# schematic_big.net
KiCad netlist of a schematic drawn in Altium Designer
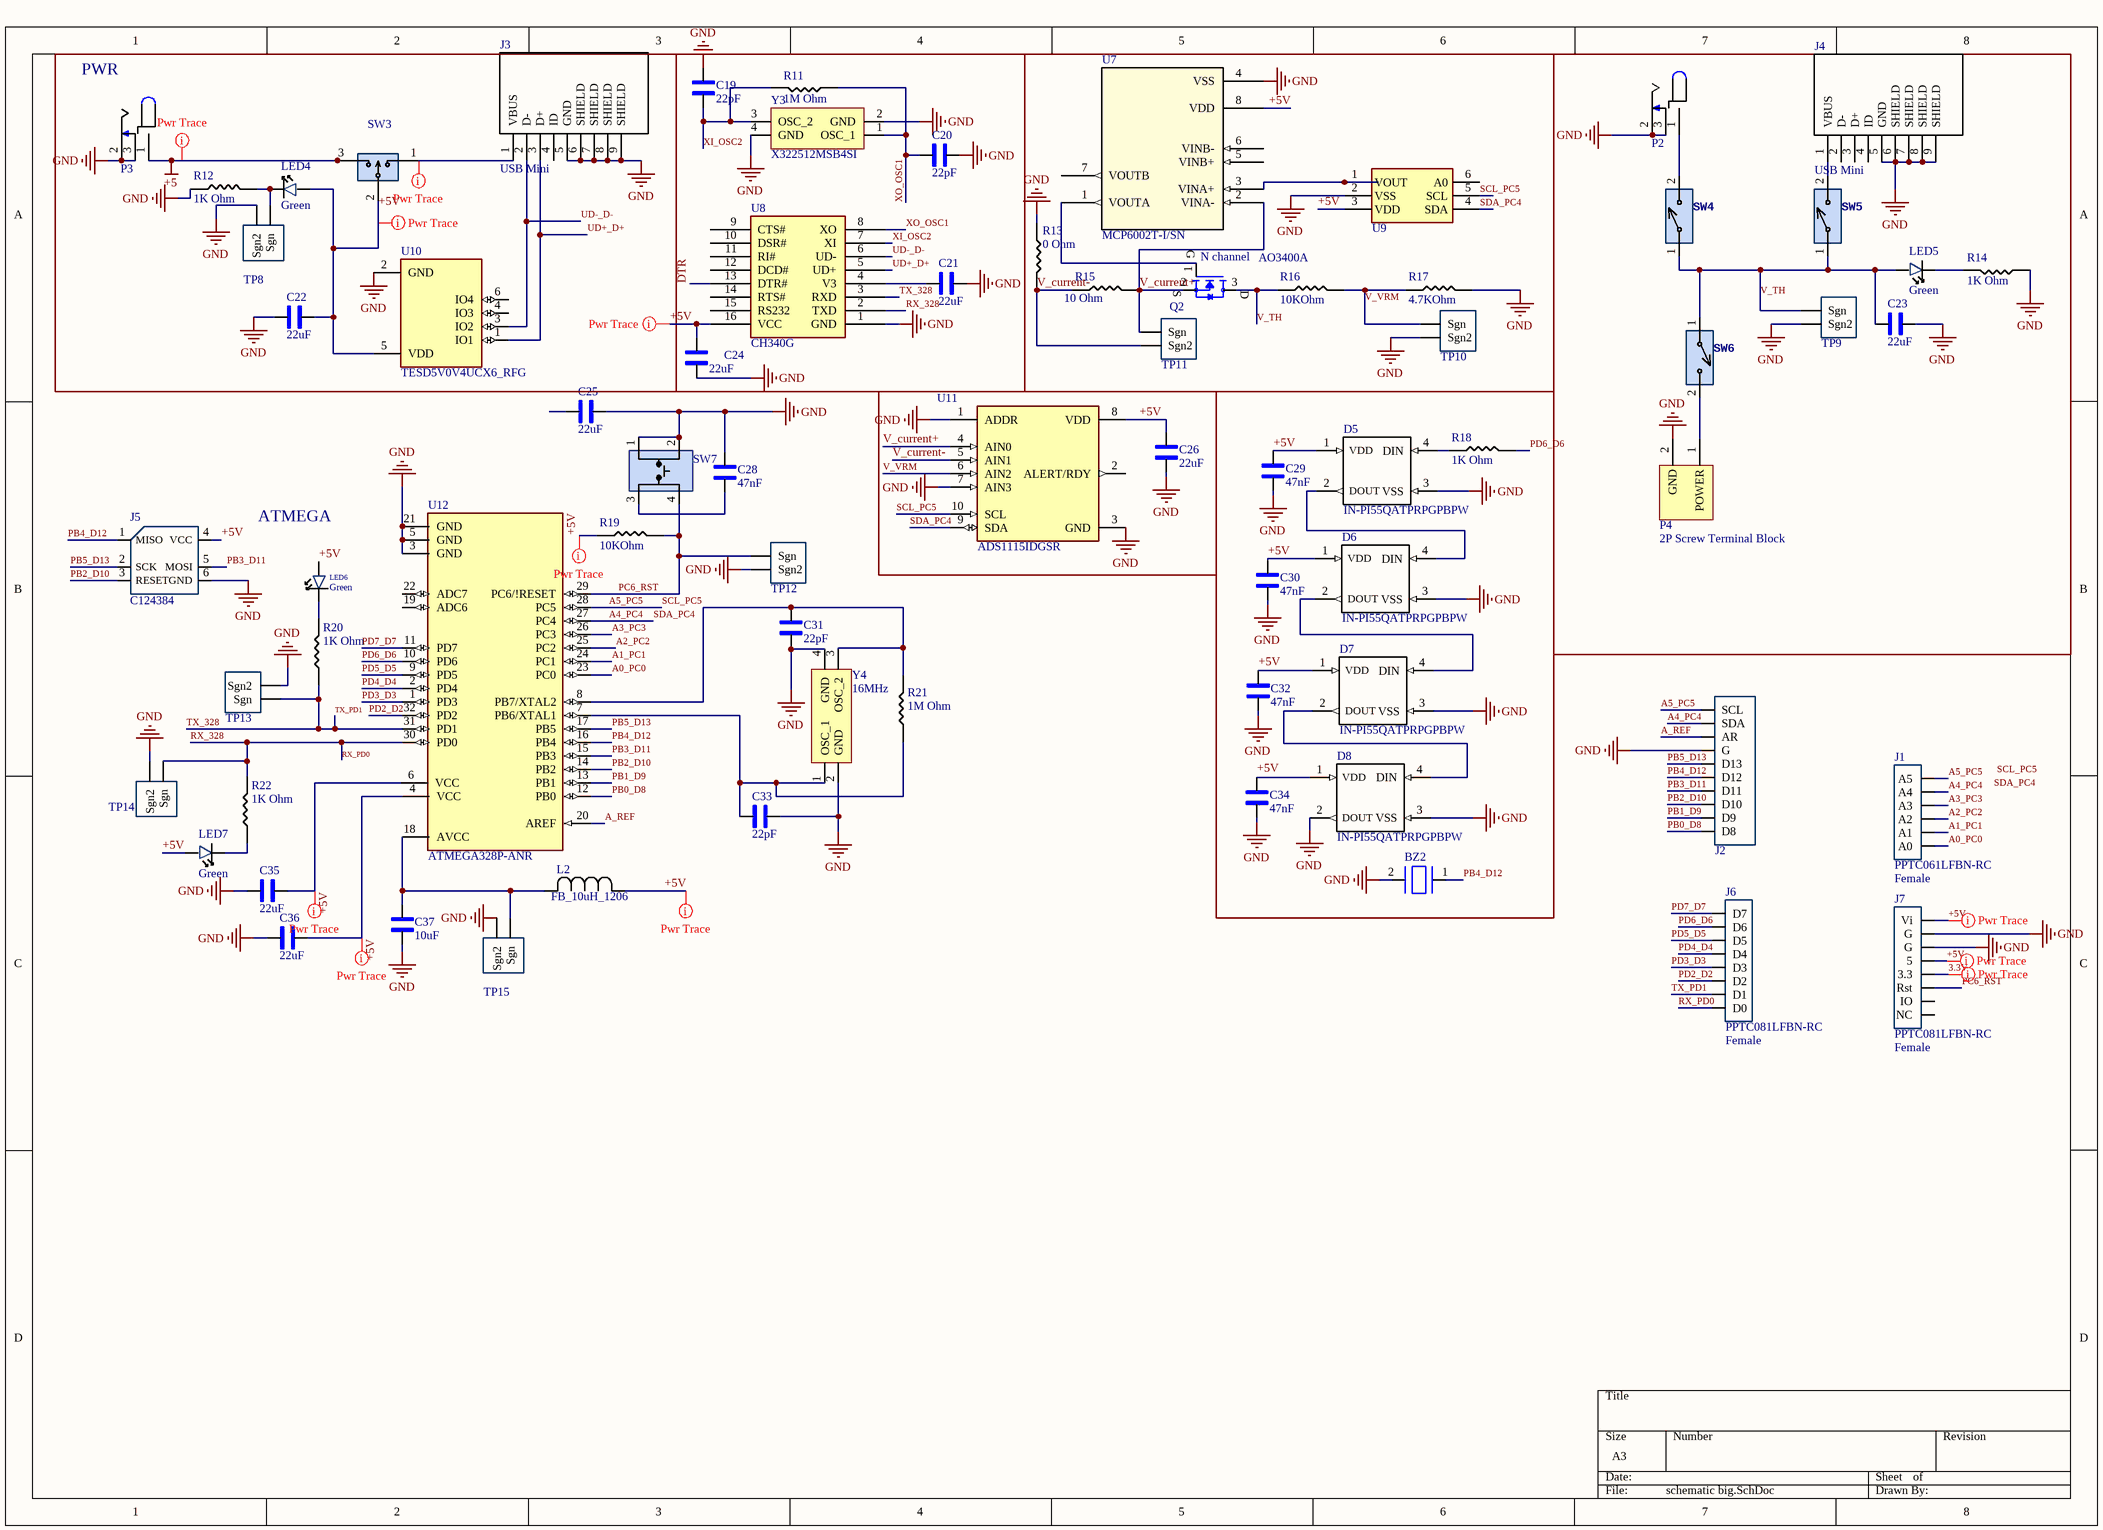
[diagram p0: schematic big.SchDoc]

(export (version "E")
  (design (tool "Eeschema 10.0.6"))
  (components
    (comp (ref "BZ2")
      (value "AT-1224-TWT-5V-2-R")
      (footprint "BUZZER- TH")
      (libsource (lib "ECEN5730Lib_2023_05_DS") (part "BUZZER_1"))
    )
    (comp (ref "C19")
      (value "22pF")
      (footprint "1206_Passive_Capacitor")
      (description "22pF ±5% 1kV C0G 1206 Multilayer Ceramic Capacitors MLCC - SMD/SMT RoHS")
      (fields (field (name "LCSC PART#") "C107174") (field (name "MFR PART #") "CC1206JKNPOCBN220"))
      (libsource (lib "ECEN5730Lib_2023_05_DS") (part "C_22pF_1206"))
    )
    (comp (ref "C20")
      (value "22pF")
      (footprint "1206_Passive_Capacitor")
      (description "22pF ±5% 1kV C0G 1206 Multilayer Ceramic Capacitors MLCC - SMD/SMT RoHS")
      (fields (field (name "LCSC PART#") "C107174") (field (name "MFR PART #") "CC1206JKNPOCBN220"))
      (libsource (lib "ECEN5730Lib_2023_05_DS") (part "C_22pF_1206"))
    )
    (comp (ref "C21")
      (value "22uF")
      (footprint "1206_Passive_Capacitor")
      (description "22uF ±10% 25V X5R 1206 Multilayer Ceramic Capacitors MLCC - SMD/SMT RoHS")
      (fields (field (name "MFR PART #") "CL31A226KAHNNNE") (field (name "LCSC PART#") "C12891"))
      (libsource (lib "ECEN5730Lib_2023_05_DS") (part "C_22uF_1206"))
    )
    (comp (ref "C22")
      (value "22uF")
      (footprint "1206_Passive_Capacitor")
      (description "22uF ±10% 25V X5R 1206 Multilayer Ceramic Capacitors MLCC - SMD/SMT RoHS")
      (fields (field (name "MFR PART #") "CL31A226KAHNNNE") (field (name "LCSC PART#") "C12891"))
      (libsource (lib "ECEN5730Lib_2023_05_DS") (part "C_22uF_1206"))
    )
    (comp (ref "C23")
      (value "22uF")
      (footprint "1206_Passive_Capacitor")
      (description "22uF ±10% 25V X5R 1206 Multilayer Ceramic Capacitors MLCC - SMD/SMT RoHS")
      (fields (field (name "MFR PART #") "CL31A226KAHNNNE") (field (name "LCSC PART#") "C12891"))
      (libsource (lib "ECEN5730Lib_2023_05_DS") (part "C_22uF_1206"))
    )
    (comp (ref "C24")
      (value "22uF")
      (footprint "1206_Passive_Capacitor")
      (description "22uF ±10% 25V X5R 1206 Multilayer Ceramic Capacitors MLCC - SMD/SMT RoHS")
      (fields (field (name "MFR PART #") "CL31A226KAHNNNE") (field (name "LCSC PART#") "C12891"))
      (libsource (lib "ECEN5730Lib_2023_05_DS") (part "C_22uF_1206"))
    )
    (comp (ref "C25")
      (value "22uF")
      (footprint "1206_Passive_Capacitor")
      (description "22uF ±10% 25V X5R 1206 Multilayer Ceramic Capacitors MLCC - SMD/SMT RoHS")
      (fields (field (name "MFR PART #") "CL31A226KAHNNNE") (field (name "LCSC PART#") "C12891"))
      (libsource (lib "ECEN5730Lib_2023_05_DS") (part "C_22uF_1206"))
    )
    (comp (ref "C26")
      (value "22uF")
      (footprint "1206_Passive_Capacitor")
      (description "22uF ±10% 25V X5R 1206 Multilayer Ceramic Capacitors MLCC - SMD/SMT RoHS")
      (fields (field (name "MFR PART #") "CL31A226KAHNNNE") (field (name "LCSC PART#") "C12891"))
      (libsource (lib "ECEN5730Lib_2023_05_DS") (part "C_22uF_1206"))
    )
    (comp (ref "C28")
      (value "47nF")
      (footprint "1206_Passive_Capacitor")
      (description "47nF ±5% 50V C0G 1206 Multilayer Ceramic Capacitors MLCC - SMD/SMT RoHS")
      (fields (field (name "LCSC PART#") "C21812") (field (name "MFR PART #") "GRM31M5C1H473JA01L"))
      (libsource (lib "ECEN5730Lib_2023_05_DS") (part "C_47nF_1206"))
    )
    (comp (ref "C29")
      (value "47nF")
      (footprint "1206_Passive_Capacitor")
      (description "47nF ±5% 50V C0G 1206 Multilayer Ceramic Capacitors MLCC - SMD/SMT RoHS")
      (fields (field (name "LCSC PART#") "C21812") (field (name "MFR PART #") "GRM31M5C1H473JA01L"))
      (libsource (lib "ECEN5730Lib_2023_05_DS") (part "C_47nF_1206"))
    )
    (comp (ref "C30")
      (value "47nF")
      (footprint "1206_Passive_Capacitor")
      (description "47nF ±5% 50V C0G 1206 Multilayer Ceramic Capacitors MLCC - SMD/SMT RoHS")
      (fields (field (name "LCSC PART#") "C21812") (field (name "MFR PART #") "GRM31M5C1H473JA01L"))
      (libsource (lib "ECEN5730Lib_2023_05_DS") (part "C_47nF_1206"))
    )
    (comp (ref "C31")
      (value "22pF")
      (footprint "1206_Passive_Capacitor")
      (description "22pF ±5% 1kV C0G 1206 Multilayer Ceramic Capacitors MLCC - SMD/SMT RoHS")
      (fields (field (name "LCSC PART#") "C107174") (field (name "MFR PART #") "CC1206JKNPOCBN220"))
      (libsource (lib "ECEN5730Lib_2023_05_DS") (part "C_22pF_1206"))
    )
    (comp (ref "C32")
      (value "47nF")
      (footprint "1206_Passive_Capacitor")
      (description "47nF ±5% 50V C0G 1206 Multilayer Ceramic Capacitors MLCC - SMD/SMT RoHS")
      (fields (field (name "LCSC PART#") "C21812") (field (name "MFR PART #") "GRM31M5C1H473JA01L"))
      (libsource (lib "ECEN5730Lib_2023_05_DS") (part "C_47nF_1206"))
    )
    (comp (ref "C33")
      (value "22pF")
      (footprint "1206_Passive_Capacitor")
      (description "22pF ±5% 1kV C0G 1206 Multilayer Ceramic Capacitors MLCC - SMD/SMT RoHS")
      (fields (field (name "LCSC PART#") "C107174") (field (name "MFR PART #") "CC1206JKNPOCBN220"))
      (libsource (lib "ECEN5730Lib_2023_05_DS") (part "C_22pF_1206"))
    )
    (comp (ref "C34")
      (value "47nF")
      (footprint "1206_Passive_Capacitor")
      (description "47nF ±5% 50V C0G 1206 Multilayer Ceramic Capacitors MLCC - SMD/SMT RoHS")
      (fields (field (name "LCSC PART#") "C21812") (field (name "MFR PART #") "GRM31M5C1H473JA01L"))
      (libsource (lib "ECEN5730Lib_2023_05_DS") (part "C_47nF_1206"))
    )
    (comp (ref "C35")
      (value "22uF")
      (footprint "1206_Passive_Capacitor")
      (description "22uF ±10% 25V X5R 1206 Multilayer Ceramic Capacitors MLCC - SMD/SMT RoHS")
      (fields (field (name "MFR PART #") "CL31A226KAHNNNE") (field (name "LCSC PART#") "C12891"))
      (libsource (lib "ECEN5730Lib_2023_05_DS") (part "C_22uF_1206"))
    )
    (comp (ref "C36")
      (value "22uF")
      (footprint "1206_Passive_Capacitor")
      (description "22uF ±10% 25V X5R 1206 Multilayer Ceramic Capacitors MLCC - SMD/SMT RoHS")
      (fields (field (name "MFR PART #") "CL31A226KAHNNNE") (field (name "LCSC PART#") "C12891"))
      (libsource (lib "ECEN5730Lib_2023_05_DS") (part "C_22uF_1206"))
    )
    (comp (ref "C37")
      (value "10uF")
      (footprint "1206_Passive_Capacitor")
      (description "10uF ±10% 50V X5R 1206 Multilayer Ceramic Capacitors MLCC - SMD/SMT RoHS")
      (fields (field (name "LCSC PART#") "C13585") (field (name "MFR PART #") "CL31A106KBHNNNE"))
      (libsource (lib "ECEN5730Lib_2023_05_DS") (part "C_10uF_1206"))
    )
    (comp (ref "D5")
      (value "IN-PI55QATPRPGPBPW")
      (footprint "SERIAL_LED - duplicate")
      (fields
        (field (name "LCSC PART#") "C2843785")
        (field (name "MFR PART #") "XL-5050RGBC-WS2812B")
        (field (name "MANUFACTURER") "XINGLIGHT")
      )
      (libsource (lib "ECEN5730Lib_2023_05_DS") (part "LED_Smart"))
    )
    (comp (ref "D6")
      (value "IN-PI55QATPRPGPBPW")
      (footprint "SERIAL_LED - duplicate")
      (fields
        (field (name "LCSC PART#") "C2843785")
        (field (name "MFR PART #") "XL-5050RGBC-WS2812B")
        (field (name "MANUFACTURER") "XINGLIGHT")
      )
      (libsource (lib "ECEN5730Lib_2023_05_DS") (part "LED_Smart"))
    )
    (comp (ref "D7")
      (value "IN-PI55QATPRPGPBPW")
      (footprint "SERIAL_LED - duplicate")
      (fields
        (field (name "LCSC PART#") "C2843785")
        (field (name "MFR PART #") "XL-5050RGBC-WS2812B")
        (field (name "MANUFACTURER") "XINGLIGHT")
      )
      (libsource (lib "ECEN5730Lib_2023_05_DS") (part "LED_Smart"))
    )
    (comp (ref "D8")
      (value "IN-PI55QATPRPGPBPW")
      (footprint "SERIAL_LED - duplicate")
      (fields
        (field (name "LCSC PART#") "C2843785")
        (field (name "MFR PART #") "XL-5050RGBC-WS2812B")
        (field (name "MANUFACTURER") "XINGLIGHT")
      )
      (libsource (lib "ECEN5730Lib_2023_05_DS") (part "LED_Smart"))
    )
    (comp (ref "J1")
      (value "PPTC061LFBN-RC")
      (footprint "6_PIN_ARD-Analog_100mil")
      (description "6 Position Header Connector 0.100\" (2.54mm) Through Hole Tin")
      (fields (field (name "LCSC PART#") "C40877") (field (name "ALTIUM_VALUE") "Female"))
      (libsource (lib "ECEN5730Lib_2023_05_DS") (part "JF_6_PIN_FEMA_ARD-Anolog"))
    )
    (comp (ref "J2")
      (value "PPTC101LFBN-RC")
      (footprint "10_PIN_ARDUINO_100MIL")
      (description "10 Position Header Connector 0.100\" (2.54mm) Through Hole Tin")
      (fields (field (name "LCSC PART#") "C225507"))
      (libsource (lib "ECEN5730Lib_2023_05_DS") (part "JF_10_PIN_FEMA_ARDUINO"))
    )
    (comp (ref "J3")
      (value "USB Mini")
      (footprint "USB_MINI_B")
      (description "Through Hole USB Connectors RoHS")
      (fields (field (name "LCSC PART#") "C46398") (field (name "MFR PART #") "920-462A2021D10102"))
      (libsource (lib "ECEN5730Lib_2023_05_DS") (part "J_USB_B_Mini"))
    )
    (comp (ref "J4")
      (value "USB Mini")
      (footprint "USB_MINI_B")
      (description "Through Hole USB Connectors RoHS")
      (fields (field (name "LCSC PART#") "C46398") (field (name "MFR PART #") "920-462A2021D10102"))
      (libsource (lib "ECEN5730Lib_2023_05_DS") (part "J_USB_B_Mini"))
    )
    (comp (ref "J5")
      (value "NRPN032PAEN-RC")
      (footprint "ICSP")
      (description "Connector Header Through Hole 6 position 0.079\" (2.00mm)")
      (fields (field (name "LCSC PART#") "C124384"))
      (libsource (lib "ECEN5730Lib_2023_05_DS") (part "J_ICSP"))
    )
    (comp (ref "J6")
      (value "PPTC081LFBN-RC")
      (footprint "8_PIN_ARD-DIG_100MIL")
      (description "8 Position Header Connector 0.100\" (2.54mm) Through Hole Tin")
      (fields (field (name "LCSC PART#") "C27438") (field (name "ALTIUM_VALUE") "Female"))
      (libsource (lib "ECEN5730Lib_2023_05_DS") (part "JF_8_PIN_FEMA_ARD-Dig"))
    )
    (comp (ref "J7")
      (value "PPTC081LFBN-RC")
      (footprint "8_PIN_ARD-PWR_100MIL")
      (description "8 Position Header Connector 0.100\" (2.54mm) Through Hole Tin")
      (fields (field (name "LCSC PART#") "C27438") (field (name "ALTIUM_VALUE") "Female"))
      (libsource (lib "ECEN5730Lib_2023_05_DS") (part "JF_8_PIN_FEMA_ARD-Pwr"))
    )
    (comp (ref "L2")
      (value "FB_10uH_1206")
      (footprint "AIML-1206_ABR-M")
      (description "25mA 10uH ±10% 800mΩ 1206  Inductors (SMD) ROHS")
      (fields (field (name "MFR PART #") "CMI321609X100KT") (field (name "LCSC PART#") "C1051"))
      (libsource (lib "ECEN5730Lib_2023_05_DS") (part "FB_10uH_1206"))
    )
    (comp (ref "LED4")
      (value "Green")
      (footprint "LED_1206")
      (description "Green 513~528nm 1206 Light Emitting Diodes (LED) RoHS")
      (fields (field (name "MFR PART #") "SZYY1206G") (field (name "LCSC PART#") "C434439"))
      (libsource (lib "ECEN5730Lib_2023_05_DS") (part "LED_GREEN_1206"))
    )
    (comp (ref "LED5")
      (value "Green")
      (footprint "LED_1206")
      (description "Green 513~528nm 1206 Light Emitting Diodes (LED) RoHS")
      (fields (field (name "MFR PART #") "SZYY1206G") (field (name "LCSC PART#") "C434439"))
      (libsource (lib "ECEN5730Lib_2023_05_DS") (part "LED_GREEN_1206"))
    )
    (comp (ref "LED6")
      (value "Green")
      (footprint "LED_1206")
      (description "Green 513~528nm 1206 Light Emitting Diodes (LED) RoHS")
      (fields (field (name "MFR PART #") "SZYY1206G") (field (name "LCSC PART#") "C434439"))
      (libsource (lib "ECEN5730Lib_2023_05_DS") (part "LED_GREEN_1206"))
    )
    (comp (ref "LED7")
      (value "Green")
      (footprint "LED_1206")
      (description "Green 513~528nm 1206 Light Emitting Diodes (LED) RoHS")
      (fields (field (name "MFR PART #") "SZYY1206G") (field (name "LCSC PART#") "C434439"))
      (libsource (lib "ECEN5730Lib_2023_05_DS") (part "LED_GREEN_1206"))
    )
    (comp (ref "P2")
      (value "Power Jack")
      (footprint "Power_Jack")
      (description "Power Barrel Connector Jack 2.10mm ID (0.083\"), 5.50mm OD (0.217\") Through Hole, Right Angle")
      (fields (field (name "MFR PART #") "PJ-102A") (field (name "LCSC PART#") "C136744"))
      (libsource (lib "ECEN5730Lib_2023_05_DS") (part "P_Power Jack"))
    )
    (comp (ref "P3")
      (value "Power Jack")
      (footprint "Power_Jack")
      (description "Power Barrel Connector Jack 2.10mm ID (0.083\"), 5.50mm OD (0.217\") Through Hole, Right Angle")
      (fields (field (name "MFR PART #") "PJ-102A") (field (name "LCSC PART#") "C136744"))
      (libsource (lib "ECEN5730Lib_2023_05_DS") (part "P_Power Jack"))
    )
    (comp (ref "P4")
      (value "2P Screw Terminal Block")
      (footprint "P_Terminal block 3.5mm-pitch")
      (description "Green Straight pin 3.5mm  pitch; P=3.5mm  Screw terminal ROHS")
      (fields (field (name "MFR PART #") "KF350-3.5-2P") (field (name "MANUFACTURER") "Cixi Kefa Elec"))
      (libsource (lib "ECEN5730Lib_2023_05_DS") (part "P_Terminal block"))
    )
    (comp (ref "Q2")
      (value "AO3400A")
      (footprint "N-MOSFET")
      (description "MOSFET N Trench 30V 5.7A 1.5V @ 250uA 26.5 m? @ 5.7A,10V SOT-23-3L RoHS")
      (fields (field (name "LCSC PART#") "C20917") (field (name "ALTIUM_VALUE") "N channel"))
      (libsource (lib "ECEN5730Lib_2023_05_DS") (part "Q_Nch_MOSFET"))
    )
    (comp (ref "R11")
      (value "1M Ohm")
      (footprint "1206_Passive_Resitor")
      (description "CHIP RESISTOR - SURFACE MOUNT 1MOHMS ±1% 1/4W 1206 ROHS")
      (fields (field (name "MFR PART #") "RMCF1206JT1M00") (field (name "LCSC PART#") "C17927"))
      (libsource (lib "ECEN5730Lib_2023_05_DS") (part "R_1M_1206"))
    )
    (comp (ref "R12")
      (value "1K Ohm")
      (footprint "1206_Passive_Resitor")
      (description "CHIP RESISTOR - SURFACE MOUNT 1KOHMS ±1% 1/4W 1206 ROHS")
      (fields (field (name "MFR PART #") "RNCP1206FTD1K00CT") (field (name "LCSC PART#") "C4410"))
      (libsource (lib "ECEN5730Lib_2023_05_DS") (part "R_1K_1206"))
    )
    (comp (ref "R13")
      (value "0 Ohm")
      (footprint "1206_Passive_Resitor")
      (description "CHIP RESISTOR - SURFACE MOUNT 0OHMS ±1% 1/4W 1206 ROHS")
      (fields (field (name "MFR PART #") "1206W4F0000T5E") (field (name "LCSC PART#") "C17888"))
      (libsource (lib "ECEN5730Lib_2023_05_DS") (part "R_0Ohm_1206"))
    )
    (comp (ref "R14")
      (value "1K Ohm")
      (footprint "1206_Passive_Resitor")
      (description "CHIP RESISTOR - SURFACE MOUNT 1KOHMS ±1% 1/4W 1206 ROHS")
      (fields (field (name "MFR PART #") "RNCP1206FTD1K00CT") (field (name "LCSC PART#") "C4410"))
      (libsource (lib "ECEN5730Lib_2023_05_DS") (part "R_1K_1206"))
    )
    (comp (ref "R15")
      (value "10 Ohm")
      (footprint "1206_Passive_Resitor")
      (description "CHIP RESISTOR - SURFACE MOUNT 0.1OHMS ±1% 1/4W 1206 ROHS")
      (fields (field (name "MFR PART #") "1206W4F100JT5E") (field (name "LCSC PART#") "C17903"))
      (libsource (lib "ECEN5730Lib_2023_05_DS") (part "R_10Ohm_1206"))
    )
    (comp (ref "R16")
      (value "10KOhm")
      (footprint "1206_Passive_Resitor")
      (description "10 kOhms ±5% 0.25W, 1/4W Chip Resistor 1206 (3216 Metric) Automotive AEC-Q200 Thick Film")
      (fields (field (name "MFR PART #") "RMCF1206FT10K0") (field (name "LCSC PART#") "C17902"))
      (libsource (lib "ECEN5730Lib_2023_05_DS") (part "R_10KOhm_1206"))
    )
    (comp (ref "R17")
      (value "4.7KOhm")
      (footprint "1206_Passive_Resitor")
      (description "4.7kΩ ±1% 0.25W ±100ppm/℃ 1206 Chip Resistor - Surface Mount RoHS")
      (fields (field (name "LCSC PART#") "C17936") (field (name "MFR PART #") "1206W4F4701T5E"))
      (libsource (lib "ECEN5730Lib_2023_05_DS") (part "R_4.7k_1206"))
    )
    (comp (ref "R18")
      (value "1K Ohm")
      (footprint "1206_Passive_Resitor")
      (description "CHIP RESISTOR - SURFACE MOUNT 1KOHMS ±1% 1/4W 1206 ROHS")
      (fields (field (name "MFR PART #") "RNCP1206FTD1K00CT") (field (name "LCSC PART#") "C4410"))
      (libsource (lib "ECEN5730Lib_2023_05_DS") (part "R_1K_1206"))
    )
    (comp (ref "R19")
      (value "10KOhm")
      (footprint "1206_Passive_Resitor")
      (description "10 kOhms ±5% 0.25W, 1/4W Chip Resistor 1206 (3216 Metric) Automotive AEC-Q200 Thick Film")
      (fields (field (name "MFR PART #") "RMCF1206FT10K0") (field (name "LCSC PART#") "C17902"))
      (libsource (lib "ECEN5730Lib_2023_05_DS") (part "R_10KOhm_1206"))
    )
    (comp (ref "R20")
      (value "1K Ohm")
      (footprint "1206_Passive_Resitor")
      (description "CHIP RESISTOR - SURFACE MOUNT 1KOHMS ±1% 1/4W 1206 ROHS")
      (fields (field (name "MFR PART #") "RNCP1206FTD1K00CT") (field (name "LCSC PART#") "C4410"))
      (libsource (lib "ECEN5730Lib_2023_05_DS") (part "R_1K_1206"))
    )
    (comp (ref "R21")
      (value "1M Ohm")
      (footprint "1206_Passive_Resitor")
      (description "CHIP RESISTOR - SURFACE MOUNT 1MOHMS ±1% 1/4W 1206 ROHS")
      (fields (field (name "MFR PART #") "RMCF1206JT1M00") (field (name "LCSC PART#") "C17927"))
      (libsource (lib "ECEN5730Lib_2023_05_DS") (part "R_1M_1206"))
    )
    (comp (ref "R22")
      (value "1K Ohm")
      (footprint "1206_Passive_Resitor")
      (description "CHIP RESISTOR - SURFACE MOUNT 1KOHMS ±1% 1/4W 1206 ROHS")
      (fields (field (name "MFR PART #") "RNCP1206FTD1K00CT") (field (name "LCSC PART#") "C4410"))
      (libsource (lib "ECEN5730Lib_2023_05_DS") (part "R_1K_1206"))
    )
    (comp (ref "SW3")
      (value "PREC003SAAN-RC")
      (footprint "3_PIN_100mil")
      (description "Connector Header Through Hole 3 position 0.100\" (2.54mm)")
      (fields (field (name "LCSC PART#") "C49257"))
      (libsource (lib "ECEN5730Lib_2023_05_DS") (part "SW_3Pin_100mil_Switch"))
    )
    (comp (ref "SW4")
      (value "SW_2Pin_100mil_Switch")
      (footprint "2Pin-Header-Conn")
      (description "2Pin Header")
      (fields (field (name "LCSC PART#") "C124375"))
      (libsource (lib "ECEN5730Lib_2023_05_DS") (part "SW_2Pin_100mil_Switch"))
    )
    (comp (ref "SW5")
      (value "SW_2Pin_100mil_Switch")
      (footprint "2Pin-Header-Conn")
      (description "2Pin Header")
      (fields (field (name "LCSC PART#") "C124375"))
      (libsource (lib "ECEN5730Lib_2023_05_DS") (part "SW_2Pin_100mil_Switch"))
    )
    (comp (ref "SW6")
      (value "SW_2Pin_100mil_Switch")
      (footprint "2Pin-Header-Conn")
      (description "2Pin Header")
      (fields (field (name "LCSC PART#") "C124375"))
      (libsource (lib "") (part "SW_2Pin_100mil_Switch_1"))
    )
    (comp (ref "SW7")
      (value "TL3305AF160QG")
      (footprint "Switch_JLC")
      (description "Tactile Switch SPST-NO Top Actuated Surface Mount")
      (fields (field (name "MFR PART #") "KH-4.5X4.5X4.3H-STM") (field (name "LCSC PART#") "C2837550"))
      (libsource (lib "ECEN5730Lib_2023_05_DS") (part "SW_Push_Button_JLC"))
    )
    (comp (ref "TP8")
      (value "10x Probe TP")
      (footprint "TP_Diff_Probe")
      (description "Test Point 300 mil centers")
      (libsource (lib "ECEN5730Lib_2023_05_DS") (part "TP_Diff_Probe"))
    )
    (comp (ref "TP9")
      (value "10x Probe TP")
      (footprint "TP_Diff_Probe")
      (description "Test Point 300 mil centers")
      (libsource (lib "") (part "TP_Diff_Probe_1"))
    )
    (comp (ref "TP10")
      (value "10x Probe TP")
      (footprint "TP_Diff_Probe")
      (description "Test Point 300 mil centers")
      (libsource (lib "") (part "TP_Diff_Probe_1"))
    )
    (comp (ref "TP11")
      (value "10x Probe TP")
      (footprint "TP_Diff_Probe")
      (description "Test Point 300 mil centers")
      (libsource (lib "") (part "TP_Diff_Probe_1"))
    )
    (comp (ref "TP12")
      (value "10x Probe TP")
      (footprint "TP_Diff_Probe")
      (description "Test Point 300 mil centers")
      (libsource (lib "") (part "TP_Diff_Probe_1"))
    )
    (comp (ref "TP13")
      (value "10x Probe TP")
      (footprint "TP_Diff_Probe")
      (description "Test Point 300 mil centers")
      (libsource (lib "") (part "TP_Diff_Probe_2"))
    )
    (comp (ref "TP14")
      (value "10x Probe TP")
      (footprint "TP_Diff_Probe")
      (description "Test Point 300 mil centers")
      (libsource (lib "ECEN5730Lib_2023_05_DS") (part "TP_Diff_Probe"))
    )
    (comp (ref "TP15")
      (value "10x Probe TP")
      (footprint "TP_Diff_Probe")
      (description "Test Point 300 mil centers")
      (libsource (lib "ECEN5730Lib_2023_05_DS") (part "TP_Diff_Probe"))
    )
    (comp (ref "U7")
      (value "MCP6002T-I/SN")
      (footprint "SOIC127P600X175-8N")
      (description "0.6 V/us 2 1MHz 1.8V ~ 6V 100μA General Purpose SOIC-8_150mil  Operational Amplifier ROHS")
      (fields (field (name "MFR") "Microchip") (field (name "LCSC PART#") "C7377"))
      (libsource (lib "ECEN5730Lib_2023_05_DS") (part "U_MCP6002T-I/SN"))
    )
    (comp (ref "U8")
      (value "CH340G")
      (footprint "USB to serial")
      (description "Transceiver USB 2.0 2Mbps SOP-16_150mil USB ICs RoHS")
      (fields (field (name "LCSC PART#") "C14267"))
      (libsource (lib "ECEN5730Lib_2023_05_DS") (part "U_USBtoSerial"))
    )
    (comp (ref "U9")
      (value "DAC IC")
      (footprint "MCP4725")
      (description "IC DAC 12BIT V-OUT SOT23-6")
      (fields (field (name "LCSC PART#") "C144198") (field (name "MFR PART #") "MCP4725A0T-E/CH"))
      (libsource (lib "ECEN5730Lib_2023_05_DS") (part "U_MCP4725A0T-E/CH"))
    )
    (comp (ref "U10")
      (value "TESD5V0V4UCX6_RFG")
      (footprint "SOT95P280X145-6N")
      (description "SOT-26, 5V, 75W, 0.6pF, ESD Protection")
      (fields (field (name "MF") "Taiwan Semiconductor") (field (name "MP") "TESD5V0V4UCX6 RFG"))
      (libsource (lib "TESD5V0V4UCX6_RFG") (part "TESD5V0V4UCX6_RFG"))
    )
    (comp (ref "U11")
      (value "ADS1115IDGSR")
      (footprint "ADC_ADS1115IDGSR")
      (description "16-Bit ADC with Integrated MUX, PGA, Comparator, Oscillator, and Reference 10-VSSOP -40 to 125")
      (fields (field (name "LCSC PART#") "C37593"))
      (libsource (lib "ECEN5730Lib_2023_05_DS") (part "U_ADC_ADS1115IDGSR"))
    )
    (comp (ref "U12")
      (value "ATMEGA328P-ANR")
      (footprint "ATMega328P")
      (description "AVR AVR® ATmega Microcontroller IC 8-Bit 20MHz 32KB (16K x 16) FLASH 32-TQFP (7x7)")
      (fields (field (name "MFR PART #") "ATMEGA328P-AU") (field (name "LCSC PART#") "C14877"))
      (libsource (lib "ECEN5730Lib_2023_05_DS") (part "U_ATMega328P"))
    )
    (comp (ref "Y3")
      (value "X322512MSB4SI")
      (footprint "Crystal resonator")
      (description "SMD Crystal Resonators 12MHz ±10ppm SMD-3225_4P RoHS")
      (fields (field (name "LCSC PART#") "C9002"))
      (libsource (lib "ECEN5730Lib_2023_05_DS") (part "X_12MHz_Res"))
    )
    (comp (ref "Y4")
      (value "16MHz")
      (footprint "Crystal resonator")
      (description "±10ppm 16000000Hz -40℃~85℃ 贴片无源晶振 60Ω 9pF SMD3225-4P Crystals ROHS")
      (fields (field (name "LCSC PART#") "C13738") (field (name "MFR PART #") "X322516MLB4SI"))
      (libsource (lib "ECEN5730Lib_2023_05_DS") (part "X_16Mhz_Res"))
    )
  )
  (nets
    (net (code "1") (name "+5") (class "Default")
      (node (ref "P3") (pin "1") (pinfunction "1_1") (pintype "power_in"))
      (node (ref "SW3") (pin "3") (pinfunction "3_3") (pintype "passive"))
    )
    (net (code "2") (name "/+5V") (class "Default")
      (node (ref "C22") (pin "2") (pinfunction "2_2") (pintype "passive"))
      (node (ref "C24") (pin "2") (pinfunction "2_2") (pintype "passive"))
      (node (ref "C26") (pin "2") (pinfunction "2_2") (pintype "passive"))
      (node (ref "C29") (pin "2") (pinfunction "2_2") (pintype "passive"))
      (node (ref "C30") (pin "2") (pinfunction "2_2") (pintype "passive"))
      (node (ref "C35") (pin "2") (pinfunction "2_2") (pintype "passive"))
      (node (ref "C36") (pin "2") (pinfunction "2_2") (pintype "passive"))
      (node (ref "D5") (pin "1") (pinfunction "VDD_1") (pintype "input"))
      (node (ref "D6") (pin "1") (pinfunction "VDD_1") (pintype "input"))
      (node (ref "J5") (pin "4") (pinfunction "VCC_4") (pintype "passive"))
      (node (ref "J7") (pin "5") (pinfunction "5_5") (pintype "passive"))
      (node (ref "J7") (pin "8") (pinfunction "Vi_8") (pintype "passive"))
      (node (ref "L2") (pin "1") (pinfunction "1_1") (pintype "passive"))
      (node (ref "LED4") (pin "1") (pinfunction "1_1") (pintype "passive"))
      (node (ref "LED6") (pin "1") (pinfunction "1_1") (pintype "passive"))
      (node (ref "LED7") (pin "1") (pinfunction "1_1") (pintype "passive"))
      (node (ref "R19") (pin "1") (pinfunction "1_1") (pintype "passive"))
      (node (ref "SW3") (pin "2") (pinfunction "2_2") (pintype "passive"))
      (node (ref "U10") (pin "5") (pinfunction "VDD_5") (pintype "power_in"))
      (node (ref "U11") (pin "8") (pinfunction "VDD_8") (pintype "power_in"))
      (node (ref "U12") (pin "4") (pinfunction "VCC_4") (pintype "power_in"))
      (node (ref "U12") (pin "6") (pinfunction "VCC_6") (pintype "power_in"))
      (node (ref "U7") (pin "8") (pinfunction "VDD_8") (pintype "passive"))
      (node (ref "U8") (pin "16") (pinfunction "VCC_16") (pintype "passive"))
      (node (ref "U9") (pin "3") (pinfunction "VDD_3") (pintype "passive"))
    )
    (net (code "3") (name "/3.3V") (class "Default")
      (node (ref "J7") (pin "4") (pinfunction "3.3_4") (pintype "passive"))
    )
    (net (code "4") (name "/A0_PC0") (class "Default")
      (node (ref "J1") (pin "1") (pinfunction "A0_1") (pintype "passive"))
      (node (ref "U12") (pin "23") (pinfunction "PC0_23") (pintype "bidirectional"))
    )
    (net (code "5") (name "/A1_PC1") (class "Default")
      (node (ref "J1") (pin "2") (pinfunction "A1_2") (pintype "passive"))
      (node (ref "U12") (pin "24") (pinfunction "PC1_24") (pintype "bidirectional"))
    )
    (net (code "6") (name "/A2_PC2") (class "Default")
      (node (ref "J1") (pin "3") (pinfunction "A2_3") (pintype "passive"))
      (node (ref "U12") (pin "25") (pinfunction "PC2_25") (pintype "bidirectional"))
    )
    (net (code "7") (name "/A3_PC3") (class "Default")
      (node (ref "J1") (pin "4") (pinfunction "A3_4") (pintype "passive"))
      (node (ref "U12") (pin "26") (pinfunction "PC3_26") (pintype "bidirectional"))
    )
    (net (code "8") (name "/A4_PC4") (class "Default")
      (node (ref "J1") (pin "5") (pinfunction "A4_5") (pintype "passive"))
      (node (ref "J2") (pin "2") (pinfunction "SDA_2") (pintype "passive"))
      (node (ref "U11") (pin "9") (pinfunction "SDA_9") (pintype "bidirectional"))
      (node (ref "U12") (pin "27") (pinfunction "PC4_27") (pintype "bidirectional"))
      (node (ref "U9") (pin "4") (pinfunction "SDA_4") (pintype "passive"))
    )
    (net (code "9") (name "/A5_PC5") (class "Default")
      (node (ref "J1") (pin "6") (pinfunction "A5_6") (pintype "passive"))
      (node (ref "J2") (pin "1") (pinfunction "SCL_1") (pintype "passive"))
      (node (ref "U11") (pin "10") (pinfunction "SCL_10") (pintype "input"))
      (node (ref "U12") (pin "28") (pinfunction "PC5_28") (pintype "bidirectional"))
      (node (ref "U9") (pin "5") (pinfunction "SCL_5") (pintype "passive"))
    )
    (net (code "10") (name "/A_REF") (class "Default")
      (node (ref "J2") (pin "3") (pinfunction "AR_3") (pintype "passive"))
      (node (ref "U12") (pin "20") (pinfunction "AREF_20") (pintype "input"))
    )
    (net (code "11") (name "/DTR") (class "Default")
      (node (ref "U8") (pin "13") (pinfunction "DTR#_13") (pintype "passive"))
    )
    (net (code "12") (name "/PB0_D8") (class "Default")
      (node (ref "J2") (pin "10") (pinfunction "D8_10") (pintype "passive"))
      (node (ref "U12") (pin "12") (pinfunction "PB0_12") (pintype "bidirectional"))
    )
    (net (code "13") (name "/PB1_D9") (class "Default")
      (node (ref "J2") (pin "9") (pinfunction "D9_9") (pintype "passive"))
      (node (ref "U12") (pin "13") (pinfunction "PB1_13") (pintype "bidirectional"))
    )
    (net (code "14") (name "/PB2_D10") (class "Default")
      (node (ref "J2") (pin "8") (pinfunction "D10_8") (pintype "passive"))
      (node (ref "J5") (pin "3") (pinfunction "RESET_3") (pintype "passive"))
      (node (ref "U12") (pin "14") (pinfunction "PB2_14") (pintype "bidirectional"))
    )
    (net (code "15") (name "/PB3_D11") (class "Default")
      (node (ref "J2") (pin "7") (pinfunction "D11_7") (pintype "passive"))
      (node (ref "J5") (pin "5") (pinfunction "MOSI_5") (pintype "passive"))
      (node (ref "U12") (pin "15") (pinfunction "PB3_15") (pintype "bidirectional"))
    )
    (net (code "16") (name "/PB4_D12") (class "Default")
      (node (ref "BZ2") (pin "1") (pinfunction "BZ1_1") (pintype "passive"))
      (node (ref "J2") (pin "6") (pinfunction "D12_6") (pintype "passive"))
      (node (ref "J5") (pin "1") (pinfunction "MISO_1") (pintype "passive"))
      (node (ref "U12") (pin "16") (pinfunction "PB4_16") (pintype "bidirectional"))
    )
    (net (code "17") (name "/PB5_D13") (class "Default")
      (node (ref "J2") (pin "5") (pinfunction "D13_5") (pintype "passive"))
      (node (ref "J5") (pin "2") (pinfunction "SCK_2") (pintype "passive"))
      (node (ref "U12") (pin "17") (pinfunction "PB5_17") (pintype "bidirectional"))
    )
    (net (code "18") (name "/PC6_RST") (class "Default")
      (node (ref "J7") (pin "3") (pinfunction "Rst_3") (pintype "passive"))
      (node (ref "R19") (pin "2") (pinfunction "2_2") (pintype "passive"))
      (node (ref "SW7") (pin "4") (pinfunction "4_4") (pintype "passive"))
      (node (ref "TP12") (pin "1") (pinfunction "Sgn_1") (pintype "passive"))
      (node (ref "U12") (pin "29") (pinfunction "PC6/!RESET_29") (pintype "bidirectional"))
    )
    (net (code "19") (name "/PD2_D2") (class "Default")
      (node (ref "J6") (pin "6") (pinfunction "D2_6") (pintype "passive"))
      (node (ref "U12") (pin "32") (pinfunction "PD2_32") (pintype "bidirectional"))
    )
    (net (code "20") (name "/PD3_D3") (class "Default")
      (node (ref "J6") (pin "5") (pinfunction "D3_5") (pintype "passive"))
      (node (ref "U12") (pin "1") (pinfunction "PD3_1") (pintype "bidirectional"))
    )
    (net (code "21") (name "/PD4_D4") (class "Default")
      (node (ref "J6") (pin "4") (pinfunction "D4_4") (pintype "passive"))
      (node (ref "U12") (pin "2") (pinfunction "PD4_2") (pintype "bidirectional"))
    )
    (net (code "22") (name "/PD5_D5") (class "Default")
      (node (ref "J6") (pin "3") (pinfunction "D5_3") (pintype "passive"))
      (node (ref "U12") (pin "9") (pinfunction "PD5_9") (pintype "bidirectional"))
    )
    (net (code "23") (name "/PD6_D6") (class "Default")
      (node (ref "J6") (pin "2") (pinfunction "D6_2") (pintype "passive"))
      (node (ref "R18") (pin "2") (pinfunction "2_2") (pintype "passive"))
      (node (ref "U12") (pin "10") (pinfunction "PD6_10") (pintype "bidirectional"))
    )
    (net (code "24") (name "/PD7_D7") (class "Default")
      (node (ref "J6") (pin "1") (pinfunction "D7_1") (pintype "passive"))
      (node (ref "U12") (pin "11") (pinfunction "PD7_11") (pintype "bidirectional"))
    )
    (net (code "25") (name "/RX_328") (class "Default")
      (node (ref "J6") (pin "8") (pinfunction "D0_8") (pintype "passive"))
      (node (ref "R22") (pin "2") (pinfunction "2_2") (pintype "passive"))
      (node (ref "TP14") (pin "1") (pinfunction "Sgn_1") (pintype "passive"))
      (node (ref "U12") (pin "30") (pinfunction "PD0_30") (pintype "bidirectional"))
      (node (ref "U8") (pin "2") (pinfunction "TXD_2") (pintype "passive"))
    )
    (net (code "26") (name "/TX_328") (class "Default")
      (node (ref "J6") (pin "7") (pinfunction "D1_7") (pintype "passive"))
      (node (ref "R20") (pin "1") (pinfunction "1_1") (pintype "passive"))
      (node (ref "TP13") (pin "1") (pinfunction "Sgn_1") (pintype "passive"))
      (node (ref "U12") (pin "31") (pinfunction "PD1_31") (pintype "bidirectional"))
      (node (ref "U8") (pin "3") (pinfunction "RXD_3") (pintype "passive"))
    )
    (net (code "27") (name "/UD+_D+") (class "Default")
      (node (ref "J3") (pin "3") (pinfunction "D+_3") (pintype "passive"))
      (node (ref "U10") (pin "1") (pinfunction "IO1_1") (pintype "bidirectional"))
      (node (ref "U8") (pin "5") (pinfunction "UD+_5") (pintype "passive"))
    )
    (net (code "28") (name "/UD-_D-") (class "Default")
      (node (ref "J3") (pin "2") (pinfunction "D-_2") (pintype "passive"))
      (node (ref "U10") (pin "3") (pinfunction "IO2_3") (pintype "bidirectional"))
      (node (ref "U8") (pin "6") (pinfunction "UD-_6") (pintype "passive"))
    )
    (net (code "29") (name "/V_TH") (class "Default")
      (node (ref "C23") (pin "2") (pinfunction "2_2") (pintype "passive"))
      (node (ref "LED5") (pin "1") (pinfunction "1_1") (pintype "passive"))
      (node (ref "Q2") (pin "3") (pinfunction "D_3") (pintype "passive"))
      (node (ref "R16") (pin "1") (pinfunction "1_1") (pintype "passive"))
      (node (ref "SW4") (pin "1") (pinfunction "1_1") (pintype "passive"))
      (node (ref "SW5") (pin "1") (pinfunction "1_1") (pintype "passive"))
      (node (ref "SW6") (pin "1") (pinfunction "1_1") (pintype "passive"))
      (node (ref "TP9") (pin "1") (pinfunction "Sgn_1") (pintype "passive"))
    )
    (net (code "30") (name "/V_VRM") (class "Default")
      (node (ref "R16") (pin "2") (pinfunction "2_2") (pintype "passive"))
      (node (ref "R17") (pin "1") (pinfunction "1_1") (pintype "passive"))
      (node (ref "TP10") (pin "1") (pinfunction "Sgn_1") (pintype "passive"))
      (node (ref "U11") (pin "6") (pinfunction "AIN2_6") (pintype "input"))
    )
    (net (code "31") (name "/V_current+") (class "Default")
      (node (ref "Q2") (pin "2") (pinfunction "S_2") (pintype "passive"))
      (node (ref "R15") (pin "2") (pinfunction "2_2") (pintype "passive"))
      (node (ref "TP11") (pin "1") (pinfunction "Sgn_1") (pintype "passive"))
      (node (ref "U11") (pin "4") (pinfunction "AIN0_4") (pintype "input"))
      (node (ref "U7") (pin "2") (pinfunction "VINA-_2") (pintype "input"))
    )
    (net (code "32") (name "/V_current-") (class "Default")
      (node (ref "R13") (pin "2") (pinfunction "2_2") (pintype "passive"))
      (node (ref "R15") (pin "1") (pinfunction "1_1") (pintype "passive"))
      (node (ref "TP11") (pin "2") (pinfunction "Sgn2_2") (pintype "passive"))
      (node (ref "U11") (pin "5") (pinfunction "AIN1_5") (pintype "input"))
    )
    (net (code "33") (name "/XI_OSC2") (class "Default")
      (node (ref "C19") (pin "2") (pinfunction "2_2") (pintype "passive"))
      (node (ref "R11") (pin "2") (pinfunction "2_2") (pintype "passive"))
      (node (ref "U8") (pin "7") (pinfunction "XI_7") (pintype "passive"))
      (node (ref "Y3") (pin "3") (pinfunction "OSC_2_3") (pintype "passive"))
    )
    (net (code "34") (name "/XO_OSC1") (class "Default")
      (node (ref "C20") (pin "1") (pinfunction "1_1") (pintype "passive"))
      (node (ref "R11") (pin "1") (pinfunction "1_1") (pintype "passive"))
      (node (ref "U8") (pin "8") (pinfunction "XO_8") (pintype "passive"))
      (node (ref "Y3") (pin "1") (pinfunction "OSC_1_1") (pintype "passive"))
    )
    (net (code "35") (name "GND") (class "Default")
      (node (ref "BZ2") (pin "2") (pinfunction "BZ2_2") (pintype "passive"))
      (node (ref "C19") (pin "1") (pinfunction "1_1") (pintype "passive"))
      (node (ref "C20") (pin "2") (pinfunction "2_2") (pintype "passive"))
      (node (ref "C21") (pin "1") (pinfunction "1_1") (pintype "passive"))
      (node (ref "C22") (pin "1") (pinfunction "1_1") (pintype "passive"))
      (node (ref "C23") (pin "1") (pinfunction "1_1") (pintype "passive"))
      (node (ref "C24") (pin "1") (pinfunction "1_1") (pintype "passive"))
      (node (ref "C25") (pin "2") (pinfunction "2_2") (pintype "passive"))
      (node (ref "C26") (pin "1") (pinfunction "1_1") (pintype "passive"))
      (node (ref "C28") (pin "2") (pinfunction "2_2") (pintype "passive"))
      (node (ref "C29") (pin "1") (pinfunction "1_1") (pintype "passive"))
      (node (ref "C30") (pin "1") (pinfunction "1_1") (pintype "passive"))
      (node (ref "C31") (pin "1") (pinfunction "1_1") (pintype "passive"))
      (node (ref "C32") (pin "1") (pinfunction "1_1") (pintype "passive"))
      (node (ref "C33") (pin "1") (pinfunction "1_1") (pintype "passive"))
      (node (ref "C34") (pin "1") (pinfunction "1_1") (pintype "passive"))
      (node (ref "C35") (pin "1") (pinfunction "1_1") (pintype "passive"))
      (node (ref "C36") (pin "1") (pinfunction "1_1") (pintype "passive"))
      (node (ref "C37") (pin "1") (pinfunction "1_1") (pintype "passive"))
      (node (ref "D5") (pin "3") (pinfunction "VSS_3") (pintype "input"))
      (node (ref "D6") (pin "3") (pinfunction "VSS_3") (pintype "input"))
      (node (ref "D7") (pin "3") (pinfunction "VSS_3") (pintype "input"))
      (node (ref "D8") (pin "2") (pinfunction "DOUT_2") (pintype "output"))
      (node (ref "D8") (pin "3") (pinfunction "VSS_3") (pintype "input"))
      (node (ref "J2") (pin "4") (pinfunction "G_4") (pintype "passive"))
      (node (ref "J3") (pin "5") (pinfunction "GND_5") (pintype "passive"))
      (node (ref "J3") (pin "6") (pinfunction "SHIELD_6") (pintype "passive"))
      (node (ref "J3") (pin "7") (pinfunction "SHIELD_7") (pintype "passive"))
      (node (ref "J3") (pin "8") (pinfunction "SHIELD_8") (pintype "passive"))
      (node (ref "J3") (pin "9") (pinfunction "SHIELD_9") (pintype "passive"))
      (node (ref "J4") (pin "5") (pinfunction "GND_5") (pintype "passive"))
      (node (ref "J4") (pin "6") (pinfunction "SHIELD_6") (pintype "passive"))
      (node (ref "J4") (pin "7") (pinfunction "SHIELD_7") (pintype "passive"))
      (node (ref "J4") (pin "8") (pinfunction "SHIELD_8") (pintype "passive"))
      (node (ref "J4") (pin "9") (pinfunction "SHIELD_9") (pintype "passive"))
      (node (ref "J5") (pin "6") (pinfunction "GND_6") (pintype "passive"))
      (node (ref "J7") (pin "6") (pinfunction "G_6") (pintype "passive"))
      (node (ref "J7") (pin "7") (pinfunction "G_7") (pintype "passive"))
      (node (ref "P2") (pin "2") (pinfunction "2_2") (pintype "power_in"))
      (node (ref "P2") (pin "3") (pinfunction "3_3") (pintype "power_in"))
      (node (ref "P3") (pin "2") (pinfunction "2_2") (pintype "power_in"))
      (node (ref "P3") (pin "3") (pinfunction "3_3") (pintype "power_in"))
      (node (ref "P4") (pin "2") (pinfunction "GND_2") (pintype "passive"))
      (node (ref "R12") (pin "1") (pinfunction "1_1") (pintype "passive"))
      (node (ref "R13") (pin "1") (pinfunction "1_1") (pintype "passive"))
      (node (ref "R14") (pin "1") (pinfunction "1_1") (pintype "passive"))
      (node (ref "R17") (pin "2") (pinfunction "2_2") (pintype "passive"))
      (node (ref "SW7") (pin "1") (pinfunction "1_1") (pintype "passive"))
      (node (ref "SW7") (pin "2") (pinfunction "2_2") (pintype "passive"))
      (node (ref "TP10") (pin "2") (pinfunction "Sgn2_2") (pintype "passive"))
      (node (ref "TP12") (pin "2") (pinfunction "Sgn2_2") (pintype "passive"))
      (node (ref "TP13") (pin "2") (pinfunction "Sgn2_2") (pintype "passive"))
      (node (ref "TP14") (pin "2") (pinfunction "Sgn2_2") (pintype "passive"))
      (node (ref "TP15") (pin "2") (pinfunction "Sgn2_2") (pintype "passive"))
      (node (ref "TP8") (pin "2") (pinfunction "Sgn2_2") (pintype "passive"))
      (node (ref "TP9") (pin "2") (pinfunction "Sgn2_2") (pintype "passive"))
      (node (ref "U10") (pin "2") (pinfunction "GND_2") (pintype "power_in"))
      (node (ref "U11") (pin "1") (pinfunction "ADDR_1") (pintype "passive"))
      (node (ref "U11") (pin "3") (pinfunction "GND_3") (pintype "power_in"))
      (node (ref "U11") (pin "7") (pinfunction "AIN3_7") (pintype "input"))
      (node (ref "U12") (pin "21") (pinfunction "GND_21") (pintype "power_in"))
      (node (ref "U12") (pin "3") (pinfunction "GND_3") (pintype "power_in"))
      (node (ref "U12") (pin "5") (pinfunction "GND_5") (pintype "power_in"))
      (node (ref "U7") (pin "4") (pinfunction "VSS_4") (pintype "passive"))
      (node (ref "U8") (pin "1") (pinfunction "GND_1") (pintype "passive"))
      (node (ref "U9") (pin "2") (pinfunction "VSS_2") (pintype "passive"))
      (node (ref "Y3") (pin "2") (pinfunction "GND_2") (pintype "passive"))
      (node (ref "Y3") (pin "4") (pinfunction "GND_4") (pintype "passive"))
      (node (ref "Y4") (pin "2") (pinfunction "GND_2") (pintype "passive"))
      (node (ref "Y4") (pin "4") (pinfunction "GND_4") (pintype "passive"))
    )
    (net (code "36") (name "Net-(C28-Pad1)") (class "Default")
      (node (ref "C28") (pin "1") (pinfunction "1_1") (pintype "passive"))
      (node (ref "SW7") (pin "3") (pinfunction "3_3") (pintype "passive"))
    )
    (net (code "37") (name "Net-(D5-DIN)") (class "Default")
      (node (ref "D5") (pin "4") (pinfunction "DIN_4") (pintype "input"))
      (node (ref "R18") (pin "1") (pinfunction "1_1") (pintype "passive"))
    )
    (net (code "38") (name "Net-(D5-DOUT)") (class "Default")
      (node (ref "D5") (pin "2") (pinfunction "DOUT_2") (pintype "output"))
      (node (ref "D6") (pin "4") (pinfunction "DIN_4") (pintype "input"))
    )
    (net (code "39") (name "Net-(D6-DOUT)") (class "Default")
      (node (ref "D6") (pin "2") (pinfunction "DOUT_2") (pintype "output"))
      (node (ref "D7") (pin "4") (pinfunction "DIN_4") (pintype "input"))
    )
    (net (code "40") (name "Net-(D7-DOUT)") (class "Default")
      (node (ref "D7") (pin "2") (pinfunction "DOUT_2") (pintype "output"))
      (node (ref "D8") (pin "4") (pinfunction "DIN_4") (pintype "input"))
    )
    (net (code "41") (name "Net-(D7-VDD)") (class "Default")
      (node (ref "C32") (pin "2") (pinfunction "2_2") (pintype "passive"))
      (node (ref "D7") (pin "1") (pinfunction "VDD_1") (pintype "input"))
    )
    (net (code "42") (name "Net-(D8-VDD)") (class "Default")
      (node (ref "C34") (pin "2") (pinfunction "2_2") (pintype "passive"))
      (node (ref "D8") (pin "1") (pinfunction "VDD_1") (pintype "input"))
    )
    (net (code "43") (name "Net-(J3-VBUS)") (class "Default")
      (node (ref "J3") (pin "1") (pinfunction "VBUS_1") (pintype "passive"))
      (node (ref "SW3") (pin "1") (pinfunction "1_1") (pintype "passive"))
    )
    (net (code "44") (name "Net-(J4-VBUS)") (class "Default")
      (node (ref "J4") (pin "1") (pinfunction "VBUS_1") (pintype "passive"))
      (node (ref "SW5") (pin "2") (pinfunction "2_2") (pintype "passive"))
    )
    (net (code "45") (name "Net-(LED5-Pad2)") (class "Default")
      (node (ref "LED5") (pin "2") (pinfunction "2_2") (pintype "passive"))
      (node (ref "R14") (pin "2") (pinfunction "2_2") (pintype "passive"))
    )
    (net (code "46") (name "Net-(LED6-Pad2)") (class "Default")
      (node (ref "LED6") (pin "2") (pinfunction "2_2") (pintype "passive"))
      (node (ref "R20") (pin "2") (pinfunction "2_2") (pintype "passive"))
    )
    (net (code "47") (name "Net-(LED7-Pad2)") (class "Default")
      (node (ref "LED7") (pin "2") (pinfunction "2_2") (pintype "passive"))
      (node (ref "R22") (pin "1") (pinfunction "1_1") (pintype "passive"))
    )
    (net (code "48") (name "Net-(P2-Pad1)") (class "Default")
      (node (ref "P2") (pin "1") (pinfunction "1_1") (pintype "power_in"))
      (node (ref "SW4") (pin "2") (pinfunction "2_2") (pintype "passive"))
    )
    (net (code "49") (name "Net-(P4-POWER)") (class "Default")
      (node (ref "P4") (pin "1") (pinfunction "POWER_1") (pintype "passive"))
      (node (ref "SW6") (pin "2") (pinfunction "2_2") (pintype "passive"))
    )
    (net (code "50") (name "Net-(Q2-G)") (class "Default")
      (node (ref "Q2") (pin "1") (pinfunction "G_1") (pintype "passive"))
      (node (ref "U7") (pin "1") (pinfunction "VOUTA_1") (pintype "output"))
    )
    (net (code "51") (name "Net-(TP8-Sgn)") (class "Default")
      (node (ref "LED4") (pin "2") (pinfunction "2_2") (pintype "passive"))
      (node (ref "R12") (pin "2") (pinfunction "2_2") (pintype "passive"))
      (node (ref "TP8") (pin "1") (pinfunction "Sgn_1") (pintype "passive"))
    )
    (net (code "52") (name "Net-(TP15-Sgn)") (class "Default")
      (node (ref "C37") (pin "2") (pinfunction "2_2") (pintype "passive"))
      (node (ref "L2") (pin "2") (pinfunction "2_2") (pintype "passive"))
      (node (ref "TP15") (pin "1") (pinfunction "Sgn_1") (pintype "passive"))
      (node (ref "U12") (pin "18") (pinfunction "AVCC_18") (pintype "power_in"))
    )
    (net (code "53") (name "Net-(U7-VINA+)") (class "Default")
      (node (ref "U7") (pin "3") (pinfunction "VINA+_3") (pintype "input"))
      (node (ref "U9") (pin "1") (pinfunction "VOUT_1") (pintype "passive"))
    )
    (net (code "54") (name "Net-(U8-V3)") (class "Default")
      (node (ref "C21") (pin "2") (pinfunction "2_2") (pintype "passive"))
      (node (ref "U8") (pin "4") (pinfunction "V3_4") (pintype "passive"))
    )
    (net (code "55") (name "Net-(U12-PB6{slash}XTAL1)") (class "Default")
      (node (ref "C33") (pin "2") (pinfunction "2_2") (pintype "passive"))
      (node (ref "R21") (pin "1") (pinfunction "1_1") (pintype "passive"))
      (node (ref "U12") (pin "7") (pinfunction "PB6/XTAL1_7") (pintype "bidirectional"))
      (node (ref "Y4") (pin "1") (pinfunction "OSC_1_1") (pintype "passive"))
    )
    (net (code "56") (name "Net-(U12-PB7{slash}XTAL2)") (class "Default")
      (node (ref "C31") (pin "2") (pinfunction "2_2") (pintype "passive"))
      (node (ref "R21") (pin "2") (pinfunction "2_2") (pintype "passive"))
      (node (ref "U12") (pin "8") (pinfunction "PB7/XTAL2_8") (pintype "bidirectional"))
      (node (ref "Y4") (pin "3") (pinfunction "OSC_2_3") (pintype "passive"))
    )
    (net (code "57") (name "unconnected-(C25-Pad1)") (class "Default")
      (node (ref "C25") (pin "1") (pinfunction "1_1") (pintype "passive"))
    )
    (net (code "58") (name "unconnected-(J3-ID-Pad4)") (class "Default")
      (node (ref "J3") (pin "4") (pinfunction "ID_4") (pintype "passive"))
    )
    (net (code "59") (name "unconnected-(J4-D+-Pad3)") (class "Default")
      (node (ref "J4") (pin "3") (pinfunction "D+_3") (pintype "passive"))
    )
    (net (code "60") (name "unconnected-(J4-D--Pad2)") (class "Default")
      (node (ref "J4") (pin "2") (pinfunction "D-_2") (pintype "passive"))
    )
    (net (code "61") (name "unconnected-(J4-ID-Pad4)") (class "Default")
      (node (ref "J4") (pin "4") (pinfunction "ID_4") (pintype "passive"))
    )
    (net (code "62") (name "unconnected-(J7-IO-Pad2)") (class "Default")
      (node (ref "J7") (pin "2") (pinfunction "IO_2") (pintype "passive"))
    )
    (net (code "63") (name "unconnected-(J7-NC-Pad1)") (class "Default")
      (node (ref "J7") (pin "1") (pinfunction "NC_1") (pintype "passive"))
    )
    (net (code "64") (name "unconnected-(U7-VINB+-Pad5)") (class "Default")
      (node (ref "U7") (pin "5") (pinfunction "VINB+_5") (pintype "input"))
    )
    (net (code "65") (name "unconnected-(U7-VINB--Pad6)") (class "Default")
      (node (ref "U7") (pin "6") (pinfunction "VINB-_6") (pintype "input"))
    )
    (net (code "66") (name "unconnected-(U7-VOUTB-Pad7)") (class "Default")
      (node (ref "U7") (pin "7") (pinfunction "VOUTB_7") (pintype "output"))
    )
    (net (code "67") (name "unconnected-(U8-CTS#-Pad9)") (class "Default")
      (node (ref "U8") (pin "9") (pinfunction "CTS#_9") (pintype "passive"))
    )
    (net (code "68") (name "unconnected-(U8-DCD#-Pad12)") (class "Default")
      (node (ref "U8") (pin "12") (pinfunction "DCD#_12") (pintype "passive"))
    )
    (net (code "69") (name "unconnected-(U8-DSR#-Pad10)") (class "Default")
      (node (ref "U8") (pin "10") (pinfunction "DSR#_10") (pintype "passive"))
    )
    (net (code "70") (name "unconnected-(U8-RI#-Pad11)") (class "Default")
      (node (ref "U8") (pin "11") (pinfunction "RI#_11") (pintype "passive"))
    )
    (net (code "71") (name "unconnected-(U8-RS232-Pad15)") (class "Default")
      (node (ref "U8") (pin "15") (pinfunction "RS232_15") (pintype "passive"))
    )
    (net (code "72") (name "unconnected-(U8-RTS#-Pad14)") (class "Default")
      (node (ref "U8") (pin "14") (pinfunction "RTS#_14") (pintype "passive"))
    )
    (net (code "73") (name "unconnected-(U9-A0-Pad6)") (class "Default")
      (node (ref "U9") (pin "6") (pinfunction "A0_6") (pintype "passive"))
    )
    (net (code "74") (name "unconnected-(U10-IO3-Pad4)") (class "Default")
      (node (ref "U10") (pin "4") (pinfunction "IO3_4") (pintype "bidirectional"))
    )
    (net (code "75") (name "unconnected-(U10-IO4-Pad6)") (class "Default")
      (node (ref "U10") (pin "6") (pinfunction "IO4_6") (pintype "bidirectional"))
    )
    (net (code "76") (name "unconnected-(U11-ALERT{slash}RDY-Pad2)") (class "Default")
      (node (ref "U11") (pin "2") (pinfunction "ALERT/RDY_2") (pintype "output"))
    )
    (net (code "77") (name "unconnected-(U12-ADC6-Pad19)") (class "Default")
      (node (ref "U12") (pin "19") (pinfunction "ADC6_19") (pintype "bidirectional"))
    )
    (net (code "78") (name "unconnected-(U12-ADC7-Pad22)") (class "Default")
      (node (ref "U12") (pin "22") (pinfunction "ADC7_22") (pintype "bidirectional"))
    )
  )
)
